# COMPLETE_SLAVE_BMS.net
KiCad netlist of a schematic drawn in Altium Designer
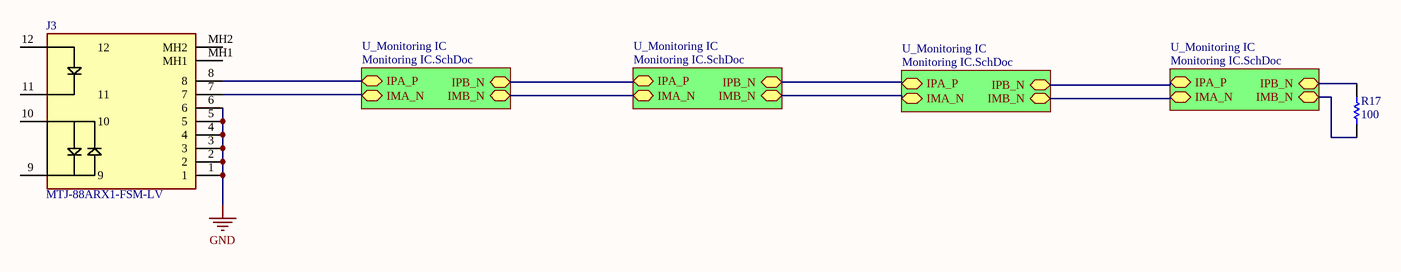
[diagram p0: COMPLETE_SLAVE_BMS.SchDoc]

(export (version "E")
  (design (tool "Eeschema 10.0.6"))
  (components
    (comp (ref "J3")
      (value "MTJ-88ARX1-FSM-LV")
      (footprint "MTJ-88ARX1-FSM-LV")
      (description "RJ45 Connector")
      (libsource (lib "GeneralConnectors") (part "MTJ-88ARX1-FSM-LV"))
    )
    (comp (ref "R17")
      (value "100")
      (footprint "0603 - Resistor")
      (description "Resistor")
      (libsource (lib "General") (part "Resistor"))
    )
  )
  (nets
    (net (code "4") (name "/IMA_N_3") (class "Default")
      (node (ref "J3") (pin "7") (pinfunction "7_7") (pintype "passive"))
    )
    (net (code "5") (name "/IMB_N") (class "Default")
      (node (ref "R17") (pin "1") (pinfunction "1_1") (pintype "passive"))
    )
    (net (code "9") (name "/IPA_P_3") (class "Default")
      (node (ref "J3") (pin "8") (pinfunction "8_8") (pintype "passive"))
    )
    (net (code "10") (name "/IPB_N") (class "Default")
      (node (ref "R17") (pin "2") (pinfunction "2_2") (pintype "passive"))
    )
    (net (code "11") (name "GND") (class "Default")
      (node (ref "J3") (pin "1") (pinfunction "1_1") (pintype "passive"))
      (node (ref "J3") (pin "2") (pinfunction "2_2") (pintype "passive"))
      (node (ref "J3") (pin "3") (pinfunction "3_3") (pintype "passive"))
      (node (ref "J3") (pin "4") (pinfunction "4_4") (pintype "passive"))
      (node (ref "J3") (pin "5") (pinfunction "5_5") (pintype "passive"))
      (node (ref "J3") (pin "6") (pinfunction "6_6") (pintype "passive"))
    )
    (net (code "12") (name "unconnected-(J3-Pad9)") (class "Default")
      (node (ref "J3") (pin "9") (pinfunction "9_9") (pintype "passive"))
    )
    (net (code "13") (name "unconnected-(J3-Pad10)") (class "Default")
      (node (ref "J3") (pin "10") (pinfunction "10_10") (pintype "passive"))
    )
    (net (code "14") (name "unconnected-(J3-Pad11)") (class "Default")
      (node (ref "J3") (pin "11") (pinfunction "11_11") (pintype "passive"))
    )
    (net (code "15") (name "unconnected-(J3-Pad12)") (class "Default")
      (node (ref "J3") (pin "12") (pinfunction "12_12") (pintype "passive"))
    )
    (net (code "16") (name "unconnected-(J3-PadMH1)") (class "Default")
      (node (ref "J3") (pin "MH1") (pinfunction "MH1_MH1") (pintype "passive"))
    )
    (net (code "17") (name "unconnected-(J3-PadMH2)") (class "Default")
      (node (ref "J3") (pin "MH2") (pinfunction "MH2_MH2") (pintype "passive"))
    )
  )
)
